# secondary.net
KiCad netlist of a schematic drawn in EAGLE
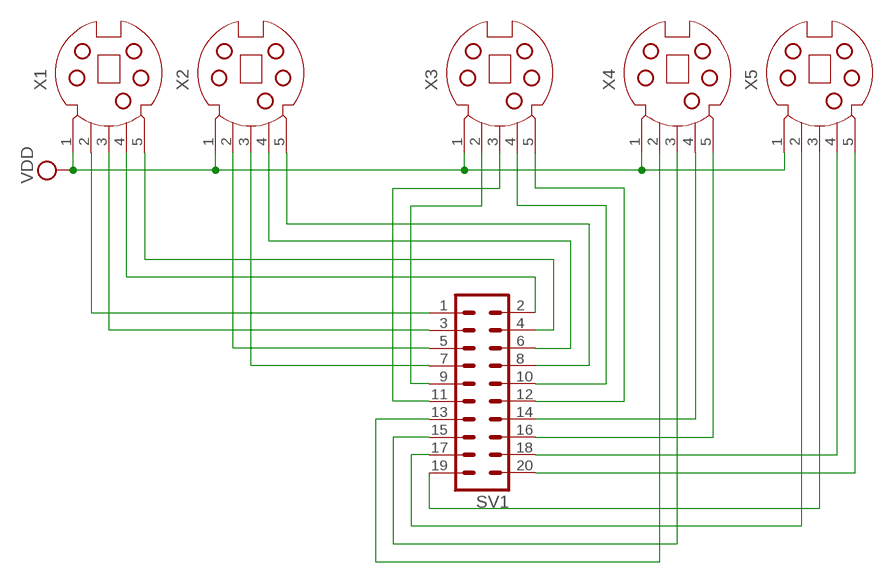
[diagram p0: schematic, sheet 1]

(export (version "E")
  (design (tool "Eeschema 10.0.6"))
  (components
    (comp (ref "SV1")
      (value "MA10-2")
      (footprint "eagle-import:MA10-2")
      (libsource (lib "eagle-import") (part "MA10-2"))
    )
    (comp (ref "X1")
      (value "MD05S")
      (footprint "eagle-import:MDIN05S")
      (libsource (lib "eagle-import") (part "MD05S"))
    )
    (comp (ref "X2")
      (value "MD05S")
      (footprint "eagle-import:MDIN05S")
      (libsource (lib "eagle-import") (part "MD05S"))
    )
    (comp (ref "X3")
      (value "MD05S")
      (footprint "eagle-import:MDIN05S")
      (libsource (lib "eagle-import") (part "MD05S"))
    )
    (comp (ref "X4")
      (value "MD05S")
      (footprint "eagle-import:MDIN05S")
      (libsource (lib "eagle-import") (part "MD05S"))
    )
    (comp (ref "X5")
      (value "MD05S")
      (footprint "eagle-import:MDIN05S")
      (libsource (lib "eagle-import") (part "MD05S"))
    )
  )
  (nets
    (net (code "1") (name "Net-(SV1-Pad1)") (class "Default")
      (node (ref "SV1") (pin "1") (pinfunction "1_1") (pintype "passive"))
      (node (ref "X1") (pin "2") (pinfunction "2_2") (pintype "passive"))
    )
    (net (code "2") (name "Net-(SV1-Pad2)") (class "Default")
      (node (ref "SV1") (pin "2") (pinfunction "2_2") (pintype "passive"))
      (node (ref "X1") (pin "4") (pinfunction "4_4") (pintype "passive"))
    )
    (net (code "3") (name "Net-(SV1-Pad3)") (class "Default")
      (node (ref "SV1") (pin "3") (pinfunction "3_3") (pintype "passive"))
      (node (ref "X1") (pin "3") (pinfunction "3_3") (pintype "passive"))
    )
    (net (code "4") (name "Net-(SV1-Pad4)") (class "Default")
      (node (ref "SV1") (pin "4") (pinfunction "4_4") (pintype "passive"))
      (node (ref "X1") (pin "5") (pinfunction "5_5") (pintype "passive"))
    )
    (net (code "5") (name "Net-(SV1-Pad5)") (class "Default")
      (node (ref "SV1") (pin "5") (pinfunction "5_5") (pintype "passive"))
      (node (ref "X2") (pin "2") (pinfunction "2_2") (pintype "passive"))
    )
    (net (code "6") (name "Net-(SV1-Pad6)") (class "Default")
      (node (ref "SV1") (pin "6") (pinfunction "6_6") (pintype "passive"))
      (node (ref "X2") (pin "4") (pinfunction "4_4") (pintype "passive"))
    )
    (net (code "7") (name "Net-(SV1-Pad7)") (class "Default")
      (node (ref "SV1") (pin "7") (pinfunction "7_7") (pintype "passive"))
      (node (ref "X2") (pin "3") (pinfunction "3_3") (pintype "passive"))
    )
    (net (code "8") (name "Net-(SV1-Pad8)") (class "Default")
      (node (ref "SV1") (pin "8") (pinfunction "8_8") (pintype "passive"))
      (node (ref "X2") (pin "5") (pinfunction "5_5") (pintype "passive"))
    )
    (net (code "9") (name "Net-(SV1-Pad9)") (class "Default")
      (node (ref "SV1") (pin "9") (pinfunction "9_9") (pintype "passive"))
      (node (ref "X3") (pin "2") (pinfunction "2_2") (pintype "passive"))
    )
    (net (code "10") (name "Net-(SV1-Pad10)") (class "Default")
      (node (ref "SV1") (pin "10") (pinfunction "10_10") (pintype "passive"))
      (node (ref "X3") (pin "4") (pinfunction "4_4") (pintype "passive"))
    )
    (net (code "11") (name "Net-(SV1-Pad11)") (class "Default")
      (node (ref "SV1") (pin "11") (pinfunction "11_11") (pintype "passive"))
      (node (ref "X3") (pin "3") (pinfunction "3_3") (pintype "passive"))
    )
    (net (code "12") (name "Net-(SV1-Pad12)") (class "Default")
      (node (ref "SV1") (pin "12") (pinfunction "12_12") (pintype "passive"))
      (node (ref "X3") (pin "5") (pinfunction "5_5") (pintype "passive"))
    )
    (net (code "13") (name "Net-(SV1-Pad13)") (class "Default")
      (node (ref "SV1") (pin "13") (pinfunction "13_13") (pintype "passive"))
      (node (ref "X4") (pin "2") (pinfunction "2_2") (pintype "passive"))
    )
    (net (code "14") (name "Net-(SV1-Pad14)") (class "Default")
      (node (ref "SV1") (pin "14") (pinfunction "14_14") (pintype "passive"))
      (node (ref "X4") (pin "4") (pinfunction "4_4") (pintype "passive"))
    )
    (net (code "15") (name "Net-(SV1-Pad15)") (class "Default")
      (node (ref "SV1") (pin "15") (pinfunction "15_15") (pintype "passive"))
      (node (ref "X4") (pin "3") (pinfunction "3_3") (pintype "passive"))
    )
    (net (code "16") (name "Net-(SV1-Pad16)") (class "Default")
      (node (ref "SV1") (pin "16") (pinfunction "16_16") (pintype "passive"))
      (node (ref "X4") (pin "5") (pinfunction "5_5") (pintype "passive"))
    )
    (net (code "17") (name "Net-(SV1-Pad17)") (class "Default")
      (node (ref "SV1") (pin "17") (pinfunction "17_17") (pintype "passive"))
      (node (ref "X5") (pin "2") (pinfunction "2_2") (pintype "passive"))
    )
    (net (code "18") (name "Net-(SV1-Pad18)") (class "Default")
      (node (ref "SV1") (pin "18") (pinfunction "18_18") (pintype "passive"))
      (node (ref "X5") (pin "4") (pinfunction "4_4") (pintype "passive"))
    )
    (net (code "19") (name "Net-(SV1-Pad19)") (class "Default")
      (node (ref "SV1") (pin "19") (pinfunction "19_19") (pintype "passive"))
      (node (ref "X5") (pin "3") (pinfunction "3_3") (pintype "passive"))
    )
    (net (code "20") (name "Net-(SV1-Pad20)") (class "Default")
      (node (ref "SV1") (pin "20") (pinfunction "20_20") (pintype "passive"))
      (node (ref "X5") (pin "5") (pinfunction "5_5") (pintype "passive"))
    )
    (net (code "21") (name "VDD") (class "Default")
      (node (ref "X1") (pin "1") (pinfunction "1_1") (pintype "passive"))
      (node (ref "X2") (pin "1") (pinfunction "1_1") (pintype "passive"))
      (node (ref "X3") (pin "1") (pinfunction "1_1") (pintype "passive"))
      (node (ref "X4") (pin "1") (pinfunction "1_1") (pintype "passive"))
      (node (ref "X5") (pin "1") (pinfunction "1_1") (pintype "passive"))
    )
  )
)
